# MLX90393_demo.net
KiCad netlist of a schematic drawn in Altium Designer
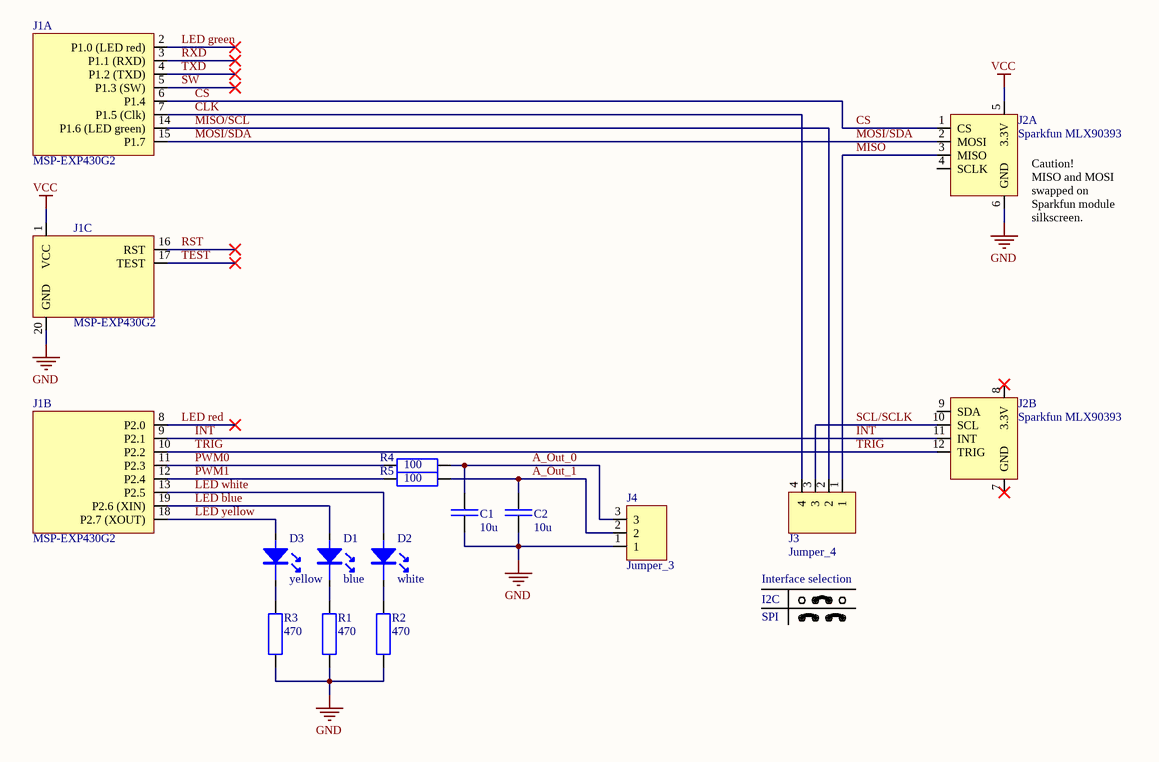
[diagram p0: MLX90393_demo.SchDoc]

(export (version "E")
  (design (tool "Eeschema 10.0.6"))
  (components
    (comp (ref "C1")
      (value "10u")
      (footprint "AMZ_Altium_Lib:C_0603_S")
      (libsource (lib "AMZ_Altium_Lib") (part "C"))
    )
    (comp (ref "C2")
      (value "10u")
      (footprint "AMZ_Altium_Lib:C_0603_S")
      (libsource (lib "AMZ_Altium_Lib") (part "C"))
    )
    (comp (ref "D1")
      (value "blue")
      (footprint "AMZ_Altium_Lib:LED_0603_S_BLUE")
      (libsource (lib "AMZ_Altium_Lib") (part "LED"))
    )
    (comp (ref "D2")
      (value "white")
      (footprint "AMZ_Altium_Lib:LED_0603_S")
      (libsource (lib "AMZ_Altium_Lib") (part "LED"))
    )
    (comp (ref "D3")
      (value "yellow")
      (footprint "AMZ_Altium_Lib:LED_0603_S_YELLOW")
      (libsource (lib "AMZ_Altium_Lib") (part "LED"))
    )
    (comp (ref "J1")
      (value "MSP-EXP430G2")
      (footprint "MLX90393_demo:MSP-EXP430G2")
      (libsource (lib "MLX90393_demo") (part "MSP-EXP430G2"))
    )
    (comp (ref "J2")
      (value "Sparkfun MLX90393")
      (footprint "MLX90393_demo:Sparkfun MLX90393")
      (libsource (lib "MLX90393_demo") (part "Sparkfun MLX90393"))
    )
    (comp (ref "J3")
      (value "Jumper_4")
      (footprint "MLX90393_demo:Jumper_4")
      (libsource (lib "MLX90393_demo") (part "Jumper_4"))
    )
    (comp (ref "J4")
      (value "Jumper_3")
      (footprint "MLX90393_demo:Jumper_3")
      (libsource (lib "MLX90393_demo") (part "Jumper_3"))
    )
    (comp (ref "R1")
      (value "470")
      (footprint "MLX90393_demo:R_conv_400mil")
      (description "Normaler Widerstand")
      (libsource (lib "AMZ_Altium_Lib") (part "R"))
    )
    (comp (ref "R2")
      (value "470")
      (footprint "MLX90393_demo:R_conv_400mil")
      (description "Normaler Widerstand")
      (libsource (lib "AMZ_Altium_Lib") (part "R"))
    )
    (comp (ref "R3")
      (value "470")
      (footprint "MLX90393_demo:R_conv_400mil")
      (description "Normaler Widerstand")
      (libsource (lib "AMZ_Altium_Lib") (part "R"))
    )
    (comp (ref "R4")
      (value "100")
      (footprint "MLX90393_demo:R_conv_400mil")
      (description "Normaler Widerstand")
      (libsource (lib "AMZ_Altium_Lib") (part "R"))
    )
    (comp (ref "R5")
      (value "100")
      (footprint "MLX90393_demo:R_conv_400mil")
      (description "Normaler Widerstand")
      (libsource (lib "AMZ_Altium_Lib") (part "R"))
    )
  )
  (nets
    (net (code "1") (name "/A_Out_0") (class "Default")
      (node (ref "C1") (pin "1") (pinfunction "1_1") (pintype "passive"))
      (node (ref "J4") (pin "3") (pinfunction "3_3") (pintype "passive"))
      (node (ref "R4") (pin "2") (pintype "passive"))
    )
    (net (code "2") (name "/A_Out_1") (class "Default")
      (node (ref "C2") (pin "1") (pinfunction "1_1") (pintype "passive"))
      (node (ref "J4") (pin "2") (pinfunction "2_2") (pintype "passive"))
      (node (ref "R5") (pin "2") (pintype "passive"))
    )
    (net (code "3") (name "/CLK") (class "Default")
      (node (ref "J1") (pin "7") (pinfunction "P1.5_(Clk)_7") (pintype "passive"))
      (node (ref "J3") (pin "4") (pinfunction "4_4") (pintype "passive"))
    )
    (net (code "4") (name "/CS") (class "Default")
      (node (ref "J1") (pin "6") (pinfunction "P1.4_6") (pintype "passive"))
      (node (ref "J2") (pin "1") (pinfunction "CS_1") (pintype "passive"))
    )
    (net (code "5") (name "/INT") (class "Default")
      (node (ref "J1") (pin "9") (pinfunction "P2.1_9") (pintype "passive"))
      (node (ref "J2") (pin "11") (pinfunction "INT_11") (pintype "passive"))
    )
    (net (code "6") (name "/LED blue") (class "Default")
      (node (ref "D1") (pin "A") (pinfunction "A_A") (pintype "passive"))
      (node (ref "J1") (pin "19") (pinfunction "P2.6_(XIN)_19") (pintype "passive"))
    )
    (net (code "7") (name "/LED green") (class "Default")
      (node (ref "J1") (pin "2") (pinfunction "P1.0_(LED_red)_2") (pintype "passive+no_connect"))
    )
    (net (code "8") (name "/LED red") (class "Default")
      (node (ref "J1") (pin "8") (pinfunction "P2.0_8") (pintype "passive+no_connect"))
    )
    (net (code "9") (name "/LED white") (class "Default")
      (node (ref "D2") (pin "A") (pinfunction "A_A") (pintype "passive"))
      (node (ref "J1") (pin "13") (pinfunction "P2.5_13") (pintype "passive"))
    )
    (net (code "10") (name "/LED yellow") (class "Default")
      (node (ref "D3") (pin "A") (pinfunction "A_A") (pintype "passive"))
      (node (ref "J1") (pin "18") (pinfunction "P2.7_(XOUT)_18") (pintype "passive"))
    )
    (net (code "11") (name "/MISO") (class "Default")
      (node (ref "J2") (pin "3") (pinfunction "MISO_3") (pintype "passive"))
      (node (ref "J3") (pin "1") (pinfunction "1_1") (pintype "passive"))
    )
    (net (code "12") (name "/MISO{slash}SCL") (class "Default")
      (node (ref "J1") (pin "14") (pinfunction "P1.6_(LED_green)_14") (pintype "passive"))
      (node (ref "J3") (pin "2") (pinfunction "2_2") (pintype "passive"))
    )
    (net (code "13") (name "/MOSI{slash}SDA") (class "Default")
      (node (ref "J1") (pin "15") (pinfunction "P1.7_15") (pintype "passive"))
      (node (ref "J2") (pin "2") (pinfunction "MOSI_2") (pintype "passive"))
    )
    (net (code "14") (name "/PWM0") (class "Default")
      (node (ref "J1") (pin "11") (pinfunction "P2.3_11") (pintype "passive"))
      (node (ref "R4") (pin "1") (pintype "passive"))
    )
    (net (code "15") (name "/PWM1") (class "Default")
      (node (ref "J1") (pin "12") (pinfunction "P2.4_12") (pintype "passive"))
      (node (ref "R5") (pin "1") (pintype "passive"))
    )
    (net (code "16") (name "/RST") (class "Default")
      (node (ref "J1") (pin "16") (pinfunction "RST_16") (pintype "passive+no_connect"))
    )
    (net (code "17") (name "/RXD") (class "Default")
      (node (ref "J1") (pin "3") (pinfunction "P1.1_(RXD)_3") (pintype "passive+no_connect"))
    )
    (net (code "18") (name "/SCL{slash}SCLK") (class "Default")
      (node (ref "J2") (pin "10") (pinfunction "SCL_10") (pintype "passive"))
      (node (ref "J3") (pin "3") (pinfunction "3_3") (pintype "passive"))
    )
    (net (code "19") (name "/SW") (class "Default")
      (node (ref "J1") (pin "5") (pinfunction "P1.3_(SW)_5") (pintype "passive+no_connect"))
    )
    (net (code "20") (name "/TEST") (class "Default")
      (node (ref "J1") (pin "17") (pinfunction "TEST_17") (pintype "passive+no_connect"))
    )
    (net (code "21") (name "/TRIG") (class "Default")
      (node (ref "J1") (pin "10") (pinfunction "P2.2_10") (pintype "passive"))
      (node (ref "J2") (pin "12") (pinfunction "TRIG_12") (pintype "passive"))
    )
    (net (code "22") (name "/TXD") (class "Default")
      (node (ref "J1") (pin "4") (pinfunction "P1.2_(TXD)_4") (pintype "passive+no_connect"))
    )
    (net (code "23") (name "GND") (class "Default")
      (node (ref "C1") (pin "2") (pinfunction "2_2") (pintype "passive"))
      (node (ref "C2") (pin "2") (pinfunction "2_2") (pintype "passive"))
      (node (ref "J1") (pin "20") (pinfunction "GND_20") (pintype "passive"))
      (node (ref "J2") (pin "6") (pinfunction "GND_6") (pintype "passive"))
      (node (ref "J4") (pin "1") (pinfunction "1_1") (pintype "passive"))
      (node (ref "R1") (pin "2") (pintype "passive"))
      (node (ref "R2") (pin "2") (pintype "passive"))
      (node (ref "R3") (pin "2") (pintype "passive"))
    )
    (net (code "24") (name "Net-(D1-PadK)") (class "Default")
      (node (ref "D1") (pin "K") (pinfunction "K_K") (pintype "passive"))
      (node (ref "R1") (pin "1") (pintype "passive"))
    )
    (net (code "25") (name "Net-(D2-PadK)") (class "Default")
      (node (ref "D2") (pin "K") (pinfunction "K_K") (pintype "passive"))
      (node (ref "R2") (pin "1") (pintype "passive"))
    )
    (net (code "26") (name "Net-(D3-PadK)") (class "Default")
      (node (ref "D3") (pin "K") (pinfunction "K_K") (pintype "passive"))
      (node (ref "R3") (pin "1") (pintype "passive"))
    )
    (net (code "27") (name "VCC") (class "Default")
      (node (ref "J1") (pin "1") (pinfunction "VCC_1") (pintype "passive"))
      (node (ref "J2") (pin "5") (pinfunction "3.3V_5") (pintype "passive"))
    )
    (net (code "28") (name "unconnected-(J2A-SCLK-Pad4)") (class "Default")
      (node (ref "J2") (pin "4") (pinfunction "SCLK_4") (pintype "passive"))
    )
    (net (code "29") (name "unconnected-(J2B-3.3V-Pad8)") (class "Default")
      (node (ref "J2") (pin "8") (pinfunction "3.3V_8") (pintype "passive+no_connect"))
    )
    (net (code "30") (name "unconnected-(J2B-GND-Pad7)") (class "Default")
      (node (ref "J2") (pin "7") (pinfunction "GND_7") (pintype "passive+no_connect"))
    )
    (net (code "31") (name "unconnected-(J2B-SDA-Pad9)") (class "Default")
      (node (ref "J2") (pin "9") (pinfunction "SDA_9") (pintype "passive"))
    )
  )
)
